# curr_meas_and_mot_conn.net
KiCad netlist of a schematic drawn in Altium Designer
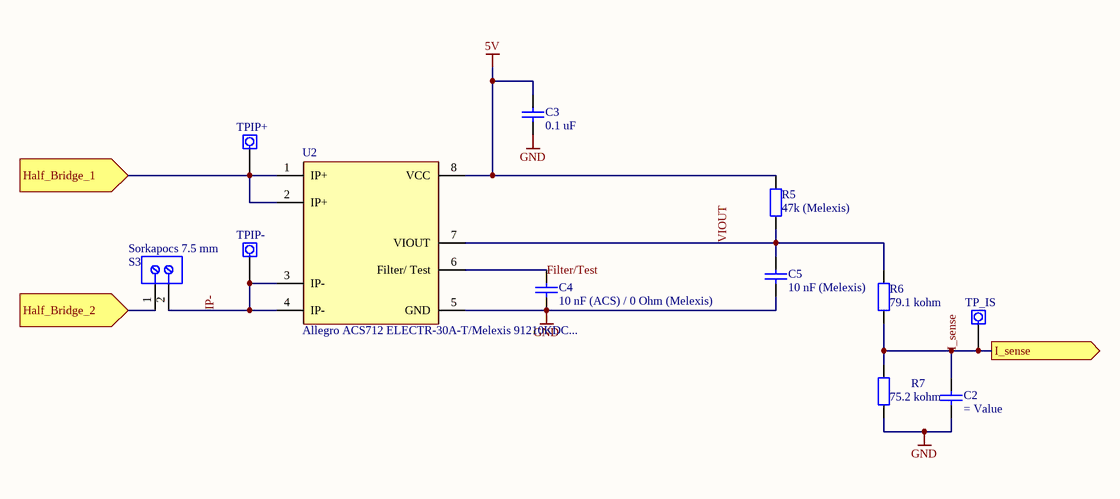
[diagram p0: curr_meas_and_mot_conn.SchDoc]

(export (version "E")
  (design (tool "Eeschema 10.0.6"))
  (components
    (comp (ref "C2") (value "~") (footprint "0805_C") (libsource (lib "PJ") (part "CAP 0805")))
    (comp (ref "C3") (value "0.1 uF") (footprint "0805_C") (libsource (lib "PJ") (part "CAP 0805")))
    (comp (ref "C4")
      (value "10 nF (ACS) / 0 Ohm (Melexis)")
      (footprint "0805_C")
      (libsource (lib "PJ") (part "CAP 0805"))
    )
    (comp (ref "C5") (value "10 nF (Melexis)") (footprint "0805_C") (libsource (lib "PJ") (part "CAP 0805")))
    (comp (ref "R5") (value "47k (Melexis)") (footprint "0805_R") (libsource (lib "PJ") (part "RES 0805")))
    (comp (ref "R6") (value "79.1 kohm") (footprint "0805_R") (libsource (lib "PJ") (part "RES 0805")))
    (comp (ref "R7") (value "75.2 kohm") (footprint "0805_R") (libsource (lib "PJ") (part "RES 0805")))
    (comp (ref "S3")
      (value "Sorkapocs 7.5 mm")
      (footprint "Sorkapocs 7.5mm")
      (libsource (lib "PJ") (part "Sorkapocs 7.5 mm"))
    )
    (comp (ref "TPIP+")
      (value "Testpoint")
      (footprint "TESTPOINT_1.5")
      (libsource (lib "PJ") (part "Testpoint"))
    )
    (comp (ref "TPIP-")
      (value "Testpoint")
      (footprint "TESTPOINT_1.5")
      (libsource (lib "PJ") (part "Testpoint"))
    )
    (comp (ref "TP_IS")
      (value "Testpoint")
      (footprint "TESTPOINT_1.5")
      (libsource (lib "PJ") (part "Testpoint"))
    )
    (comp (ref "U2")
      (value "Allegro ACS712 ELECTR-30A-T/Melexis 91210KDC...")
      (footprint "SO-8")
      (description "Áram mérő hall elemes szenzorok, 5V-os tápfeszültséggel")
      (libsource (lib "PJ") (part "Allegro ACS712 ELECTR-30A-T/Melexis 91210KDC..."))
    )
  )
  (nets
    (net (code "1") (name "/Filter{slash}Test") (class "Default")
      (node (ref "C4") (pin "1") (pinfunction "1_1") (pintype "passive"))
      (node (ref "U2") (pin "6") (pinfunction "Filter/_Test_6") (pintype "passive"))
    )
    (net (code "2") (name "/Half_Bridge_1") (class "Default")
      (node (ref "TPIP+") (pin "1") (pinfunction "1_1") (pintype "passive"))
      (node (ref "U2") (pin "1") (pinfunction "IP+_1") (pintype "passive"))
      (node (ref "U2") (pin "2") (pinfunction "IP+_2") (pintype "passive"))
    )
    (net (code "3") (name "/Half_Bridge_2") (class "Default")
      (node (ref "S3") (pin "1") (pinfunction "1_1") (pintype "passive"))
    )
    (net (code "4") (name "/IP-") (class "Default")
      (node (ref "S3") (pin "2") (pinfunction "2_2") (pintype "passive"))
      (node (ref "TPIP-") (pin "1") (pinfunction "1_1") (pintype "passive"))
      (node (ref "U2") (pin "3") (pinfunction "IP-_3") (pintype "passive"))
      (node (ref "U2") (pin "4") (pinfunction "IP-_4") (pintype "passive"))
    )
    (net (code "5") (name "/I_sense") (class "Default")
      (node (ref "C2") (pin "1") (pinfunction "1_1") (pintype "passive"))
      (node (ref "R6") (pin "1") (pinfunction "1_1") (pintype "passive"))
      (node (ref "R7") (pin "2") (pinfunction "2_2") (pintype "passive"))
      (node (ref "TP_IS") (pin "1") (pinfunction "1_1") (pintype "passive"))
    )
    (net (code "6") (name "/VIOUT") (class "Default")
      (node (ref "C5") (pin "1") (pinfunction "1_1") (pintype "passive"))
      (node (ref "R5") (pin "1") (pinfunction "1_1") (pintype "passive"))
      (node (ref "R6") (pin "2") (pinfunction "2_2") (pintype "passive"))
      (node (ref "U2") (pin "7") (pinfunction "VIOUT_7") (pintype "passive"))
    )
    (net (code "7") (name "5V") (class "Default")
      (node (ref "C3") (pin "2") (pinfunction "2_2") (pintype "passive"))
      (node (ref "R5") (pin "2") (pinfunction "2_2") (pintype "passive"))
      (node (ref "U2") (pin "8") (pinfunction "VCC_8") (pintype "power_in"))
    )
    (net (code "8") (name "GND") (class "Default")
      (node (ref "C2") (pin "2") (pinfunction "2_2") (pintype "passive"))
      (node (ref "C3") (pin "1") (pinfunction "1_1") (pintype "passive"))
      (node (ref "C4") (pin "2") (pinfunction "2_2") (pintype "passive"))
      (node (ref "C5") (pin "2") (pinfunction "2_2") (pintype "passive"))
      (node (ref "R7") (pin "1") (pinfunction "1_1") (pintype "passive"))
      (node (ref "U2") (pin "5") (pinfunction "GND_5") (pintype "passive"))
    )
  )
)
